# 17_RK3588_HDMI_eDP_Interface.net
KiCad netlist of a schematic drawn in Altium Designer
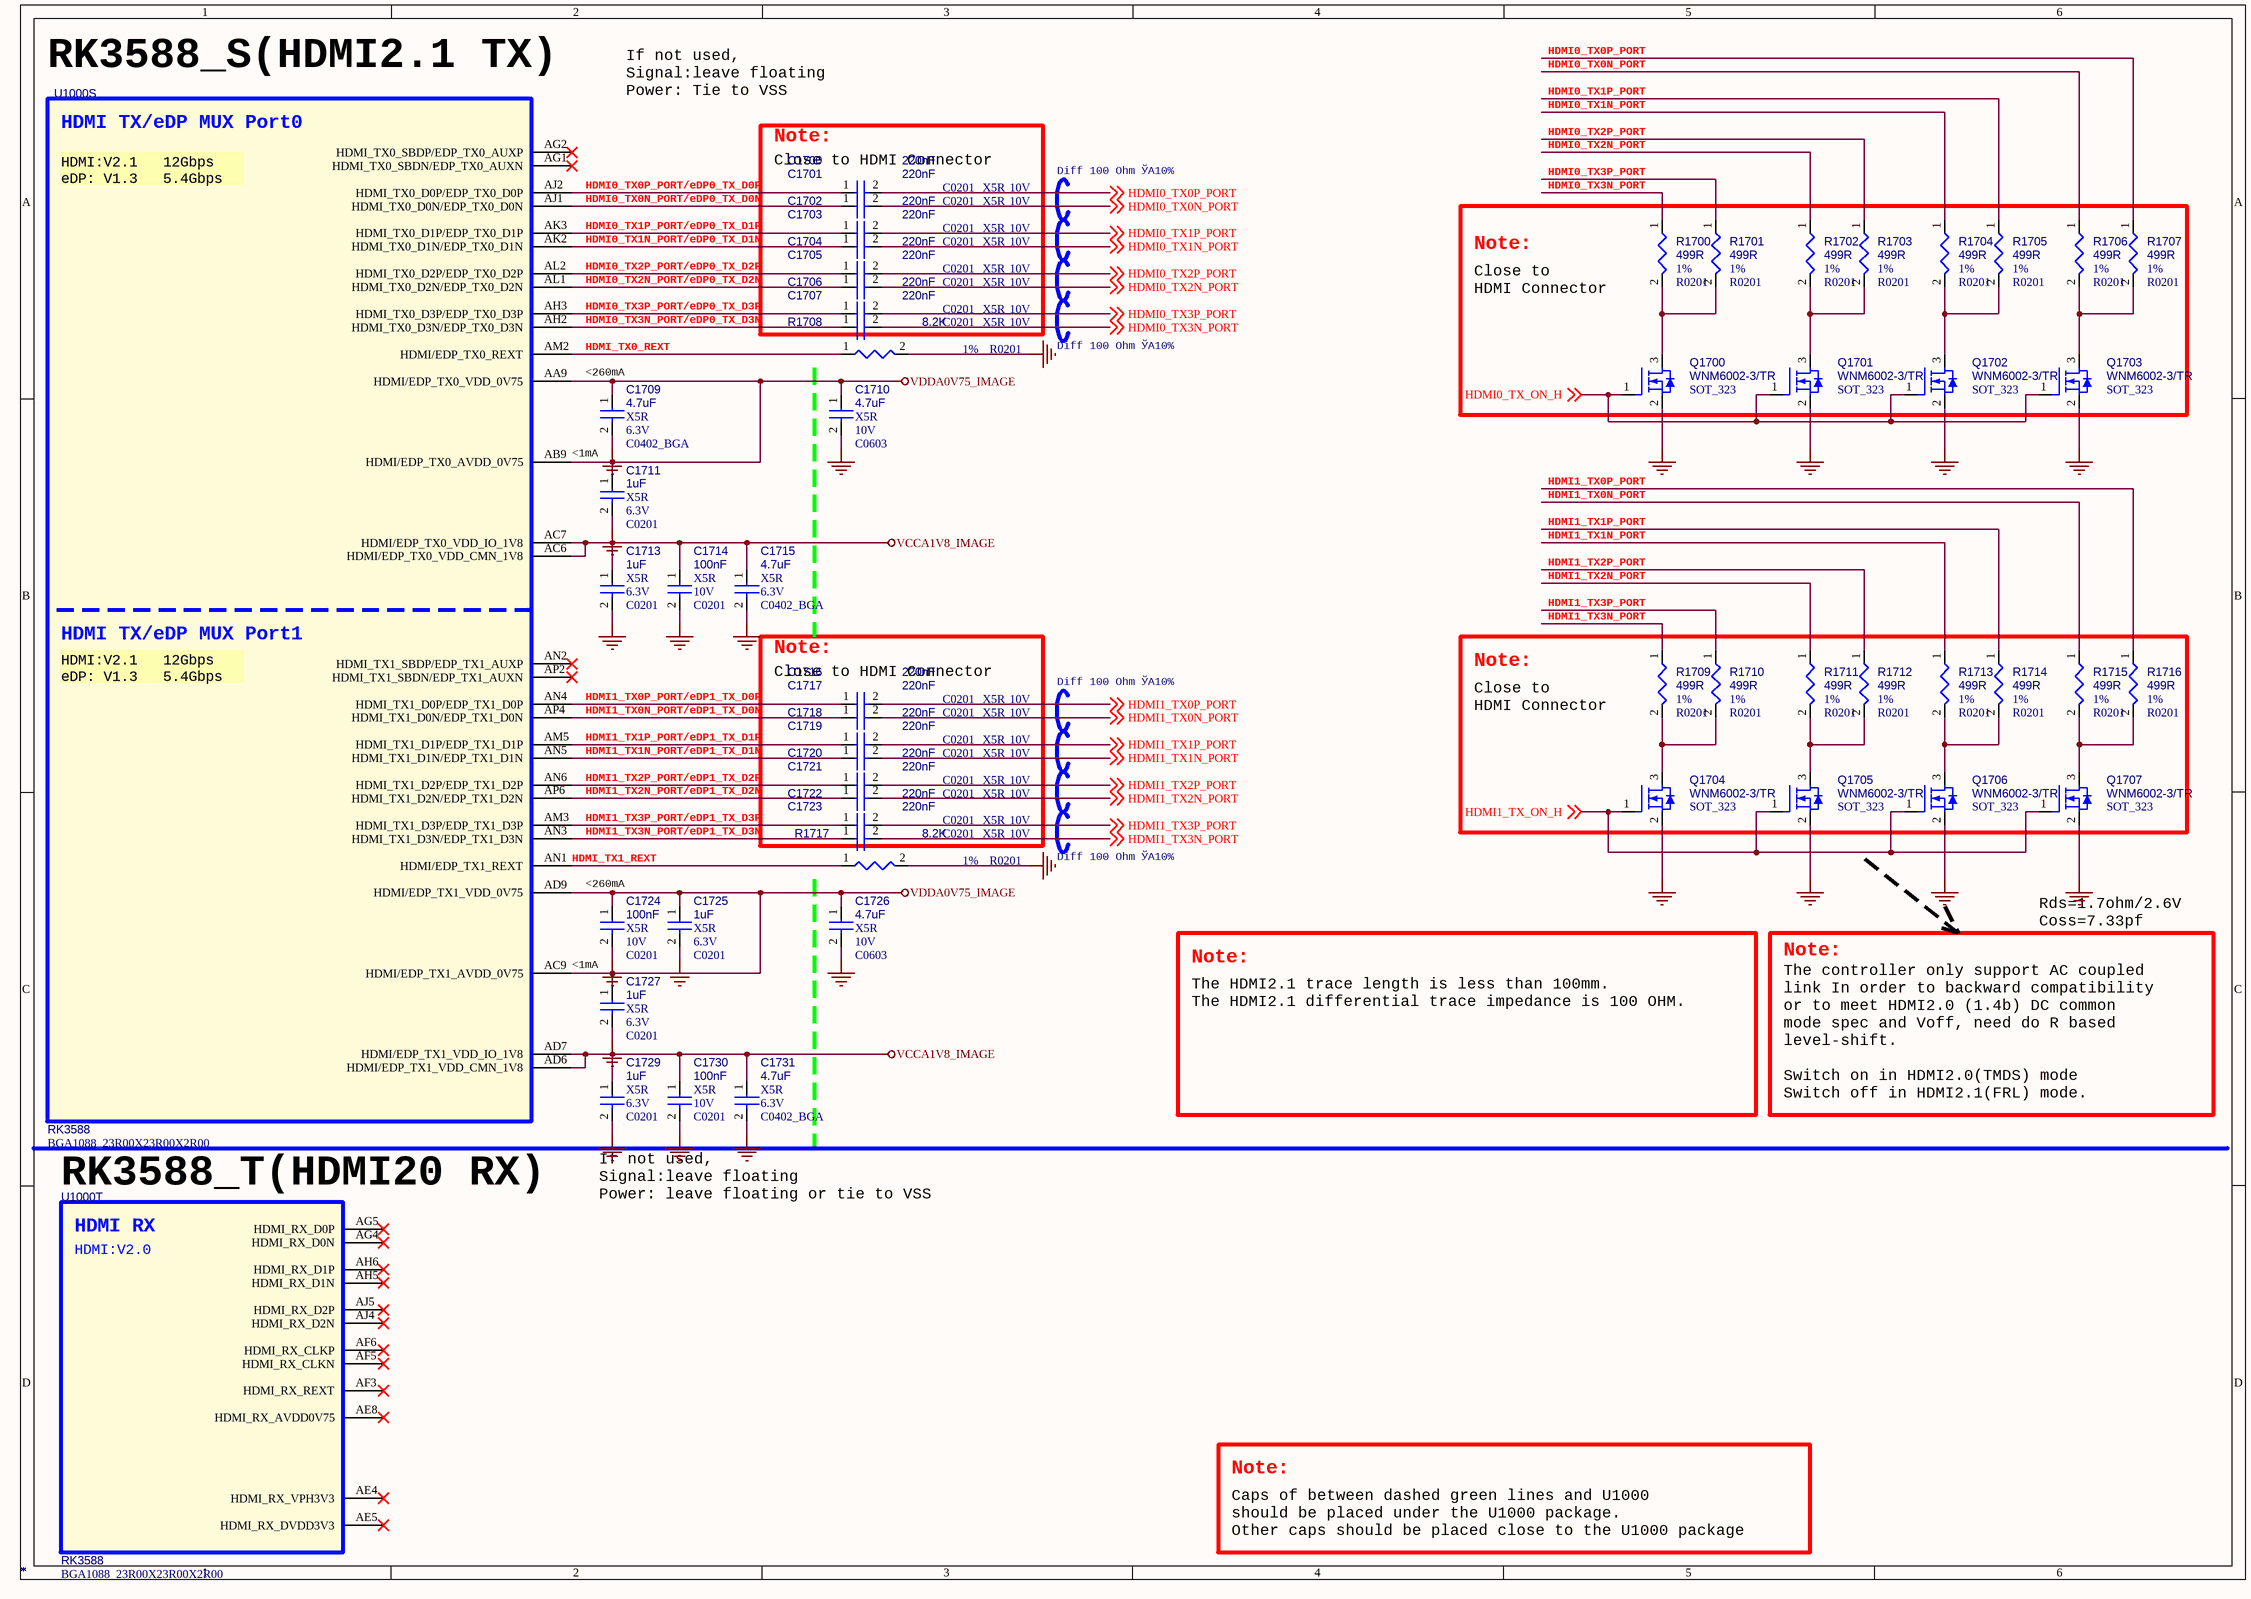
[diagram p0: 17.RK3588_HDMI_eDP Interface.SchDoc]

(export (version "E")
  (design (tool "Eeschema 10.0.6"))
  (components
    (comp (ref "C1700")
      (value "*")
      (footprint "C0201")
      (description "cap,220.00nF,+/-10%,10V,X5R,C0201")
      (fields
        (field (name "VOLTAGE") "10V")
        (field (name "PCB FOOTPRINT") "C0201")
        (field (name "DIELECTRIC") "X5R")
        (field (name "TOLERANCE") "10%")
        (field (name "MANUFACTURER") "TDK")
        (field (name "ALTIUM_UNNAMED_1") "220nF")
        (field (name "CREATED BY") "JJJ")
      )
      (libsource (lib "*") (part "CAP NP"))
    )
    (comp (ref "C1701")
      (value "*")
      (footprint "C0201")
      (description "cap,220.00nF,+/-10%,10V,X5R,C0201")
      (fields
        (field (name "VOLTAGE") "10V")
        (field (name "PCB FOOTPRINT") "C0201")
        (field (name "DIELECTRIC") "X5R")
        (field (name "MANUFACTURER") "TDK")
        (field (name "TOLERANCE") "10%")
        (field (name "ALTIUM_UNNAMED_1") "220nF")
        (field (name "CREATED BY") "JJJ")
      )
      (libsource (lib "*") (part "CAP NP"))
    )
    (comp (ref "C1702")
      (value "*")
      (footprint "C0201")
      (description "cap,220.00nF,+/-10%,10V,X5R,C0201")
      (fields
        (field (name "VOLTAGE") "10V")
        (field (name "PCB FOOTPRINT") "C0201")
        (field (name "DIELECTRIC") "X5R")
        (field (name "TOLERANCE") "10%")
        (field (name "MANUFACTURER") "TDK")
        (field (name "ALTIUM_UNNAMED_1") "220nF")
        (field (name "CREATED BY") "JJJ")
      )
      (libsource (lib "*") (part "CAP NP"))
    )
    (comp (ref "C1703")
      (value "*")
      (footprint "C0201")
      (description "cap,220.00nF,+/-10%,10V,X5R,C0201")
      (fields
        (field (name "VOLTAGE") "10V")
        (field (name "PCB FOOTPRINT") "C0201")
        (field (name "DIELECTRIC") "X5R")
        (field (name "MANUFACTURER") "TDK")
        (field (name "TOLERANCE") "10%")
        (field (name "ALTIUM_UNNAMED_1") "220nF")
        (field (name "CREATED BY") "JJJ")
      )
      (libsource (lib "*") (part "CAP NP"))
    )
    (comp (ref "C1704")
      (value "*")
      (footprint "C0201")
      (description "cap,220.00nF,+/-10%,10V,X5R,C0201")
      (fields
        (field (name "VOLTAGE") "10V")
        (field (name "PCB FOOTPRINT") "C0201")
        (field (name "DIELECTRIC") "X5R")
        (field (name "TOLERANCE") "10%")
        (field (name "MANUFACTURER") "TDK")
        (field (name "ALTIUM_UNNAMED_1") "220nF")
        (field (name "CREATED BY") "JJJ")
      )
      (libsource (lib "*") (part "CAP NP"))
    )
    (comp (ref "C1705")
      (value "*")
      (footprint "C0201")
      (description "cap,220.00nF,+/-10%,10V,X5R,C0201")
      (fields
        (field (name "VOLTAGE") "10V")
        (field (name "PCB FOOTPRINT") "C0201")
        (field (name "DIELECTRIC") "X5R")
        (field (name "MANUFACTURER") "TDK")
        (field (name "TOLERANCE") "10%")
        (field (name "ALTIUM_UNNAMED_1") "220nF")
        (field (name "CREATED BY") "JJJ")
      )
      (libsource (lib "*") (part "CAP NP"))
    )
    (comp (ref "C1706")
      (value "*")
      (footprint "C0201")
      (description "cap,220.00nF,+/-10%,10V,X5R,C0201")
      (fields
        (field (name "VOLTAGE") "10V")
        (field (name "PCB FOOTPRINT") "C0201")
        (field (name "DIELECTRIC") "X5R")
        (field (name "TOLERANCE") "10%")
        (field (name "MANUFACTURER") "TDK")
        (field (name "ALTIUM_UNNAMED_1") "220nF")
        (field (name "CREATED BY") "JJJ")
      )
      (libsource (lib "*") (part "CAP NP"))
    )
    (comp (ref "C1707")
      (value "*")
      (footprint "C0201")
      (description "cap,220.00nF,+/-10%,10V,X5R,C0201")
      (fields
        (field (name "VOLTAGE") "10V")
        (field (name "PCB FOOTPRINT") "C0201")
        (field (name "DIELECTRIC") "X5R")
        (field (name "TOLERANCE") "10%")
        (field (name "MANUFACTURER") "TDK")
        (field (name "ALTIUM_UNNAMED_1") "220nF")
        (field (name "CREATED BY") "JJJ")
      )
      (libsource (lib "*") (part "CAP NP"))
    )
    (comp (ref "C1709")
      (value "*")
      (footprint "C0402_BGA")
      (description "cap,4.70uF,+/-10%,6.3V,X5R,C0402")
      (fields
        (field (name "VOLTAGE") "6.3V")
        (field (name "PCB FOOTPRINT") "C0402_BGA")
        (field (name "DIELECTRIC") "X5R")
        (field (name "MANUFACTURER") "TDK")
        (field (name "TOLERANCE") "10%")
        (field (name "ALTIUM_UNNAMED_1") "4.7uF")
        (field (name "CREATED BY") "JJJ")
      )
      (libsource (lib "*") (part "CAP NP"))
    )
    (comp (ref "C1710")
      (value "*")
      (footprint "C0603")
      (description "cap,4.70uF,+/-10%,10V,X5R,C0603")
      (fields
        (field (name "VOLTAGE") "10V")
        (field (name "PCB FOOTPRINT") "C0603")
        (field (name "DIELECTRIC") "X5R")
        (field (name "MANUFACTURER") "TDK")
        (field (name "TOLERANCE") "10%")
        (field (name "ALTIUM_UNNAMED_1") "4.7uF")
        (field (name "CREATED BY") "JJJ")
      )
      (libsource (lib "*") (part "CAP NP"))
    )
    (comp (ref "C1711")
      (value "*")
      (footprint "C0201")
      (description "cap,1.00uF,+/-20%,6.3V,X5R,C0201")
      (fields
        (field (name "VOLTAGE") "6.3V")
        (field (name "PCB FOOTPRINT") "C0201")
        (field (name "DIELECTRIC") "X5R")
        (field (name "MANUFACTURER") "TDK")
        (field (name "TOLERANCE") "20%")
        (field (name "ALTIUM_UNNAMED_1") "1uF")
        (field (name "CREATED BY") "JJJ")
      )
      (libsource (lib "*") (part "CAP NP"))
    )
    (comp (ref "C1713")
      (value "*")
      (footprint "C0201")
      (description "cap,1.00uF,+/-20%,6.3V,X5R,C0201")
      (fields
        (field (name "VOLTAGE") "6.3V")
        (field (name "PCB FOOTPRINT") "C0201")
        (field (name "DIELECTRIC") "X5R")
        (field (name "TOLERANCE") "20%")
        (field (name "MANUFACTURER") "TDK")
        (field (name "ALTIUM_UNNAMED_1") "1uF")
        (field (name "CREATED BY") "JJJ")
      )
      (libsource (lib "*") (part "CAP NP"))
    )
    (comp (ref "C1714")
      (value "*")
      (footprint "C0201")
      (description "cap,100.00nF,+/-10%,10V,X5R,C0201")
      (fields
        (field (name "VOLTAGE") "10V")
        (field (name "PCB FOOTPRINT") "C0201")
        (field (name "DIELECTRIC") "X5R")
        (field (name "MANUFACTURER") "TDK")
        (field (name "TOLERANCE") "10%")
        (field (name "ALTIUM_UNNAMED_1") "100nF")
        (field (name "CREATED BY") "JJJ")
      )
      (libsource (lib "*") (part "CAP NP"))
    )
    (comp (ref "C1715")
      (value "*")
      (footprint "C0402_BGA")
      (description "cap,4.70uF,+/-10%,6.3V,X5R,C0402")
      (fields
        (field (name "VOLTAGE") "6.3V")
        (field (name "PCB FOOTPRINT") "C0402_BGA")
        (field (name "DIELECTRIC") "X5R")
        (field (name "TOLERANCE") "10%")
        (field (name "MANUFACTURER") "TDK")
        (field (name "ALTIUM_UNNAMED_1") "4.7uF")
        (field (name "CREATED BY") "JJJ")
      )
      (libsource (lib "*") (part "CAP NP"))
    )
    (comp (ref "C1716")
      (value "*")
      (footprint "C0201")
      (description "cap,220.00nF,+/-10%,10V,X5R,C0201")
      (fields
        (field (name "VOLTAGE") "10V")
        (field (name "PCB FOOTPRINT") "C0201")
        (field (name "DIELECTRIC") "X5R")
        (field (name "TOLERANCE") "10%")
        (field (name "MANUFACTURER") "TDK")
        (field (name "ALTIUM_UNNAMED_1") "220nF")
        (field (name "CREATED BY") "JJJ")
      )
      (libsource (lib "*") (part "CAP NP"))
    )
    (comp (ref "C1717")
      (value "*")
      (footprint "C0201")
      (description "cap,220.00nF,+/-10%,10V,X5R,C0201")
      (fields
        (field (name "VOLTAGE") "10V")
        (field (name "PCB FOOTPRINT") "C0201")
        (field (name "DIELECTRIC") "X5R")
        (field (name "MANUFACTURER") "TDK")
        (field (name "TOLERANCE") "10%")
        (field (name "ALTIUM_UNNAMED_1") "220nF")
        (field (name "CREATED BY") "JJJ")
      )
      (libsource (lib "*") (part "CAP NP"))
    )
    (comp (ref "C1718")
      (value "*")
      (footprint "C0201")
      (description "cap,220.00nF,+/-10%,10V,X5R,C0201")
      (fields
        (field (name "VOLTAGE") "10V")
        (field (name "PCB FOOTPRINT") "C0201")
        (field (name "DIELECTRIC") "X5R")
        (field (name "TOLERANCE") "10%")
        (field (name "MANUFACTURER") "TDK")
        (field (name "ALTIUM_UNNAMED_1") "220nF")
        (field (name "CREATED BY") "JJJ")
      )
      (libsource (lib "*") (part "CAP NP"))
    )
    (comp (ref "C1719")
      (value "*")
      (footprint "C0201")
      (description "cap,220.00nF,+/-10%,10V,X5R,C0201")
      (fields
        (field (name "VOLTAGE") "10V")
        (field (name "PCB FOOTPRINT") "C0201")
        (field (name "DIELECTRIC") "X5R")
        (field (name "MANUFACTURER") "TDK")
        (field (name "TOLERANCE") "10%")
        (field (name "ALTIUM_UNNAMED_1") "220nF")
        (field (name "CREATED BY") "JJJ")
      )
      (libsource (lib "*") (part "CAP NP"))
    )
    (comp (ref "C1720")
      (value "*")
      (footprint "C0201")
      (description "cap,220.00nF,+/-10%,10V,X5R,C0201")
      (fields
        (field (name "VOLTAGE") "10V")
        (field (name "PCB FOOTPRINT") "C0201")
        (field (name "DIELECTRIC") "X5R")
        (field (name "TOLERANCE") "10%")
        (field (name "MANUFACTURER") "TDK")
        (field (name "ALTIUM_UNNAMED_1") "220nF")
        (field (name "CREATED BY") "JJJ")
      )
      (libsource (lib "*") (part "CAP NP"))
    )
    (comp (ref "C1721")
      (value "*")
      (footprint "C0201")
      (description "cap,220.00nF,+/-10%,10V,X5R,C0201")
      (fields
        (field (name "VOLTAGE") "10V")
        (field (name "PCB FOOTPRINT") "C0201")
        (field (name "DIELECTRIC") "X5R")
        (field (name "MANUFACTURER") "TDK")
        (field (name "TOLERANCE") "10%")
        (field (name "ALTIUM_UNNAMED_1") "220nF")
        (field (name "CREATED BY") "JJJ")
      )
      (libsource (lib "*") (part "CAP NP"))
    )
    (comp (ref "C1722")
      (value "*")
      (footprint "C0201")
      (description "cap,220.00nF,+/-10%,10V,X5R,C0201")
      (fields
        (field (name "VOLTAGE") "10V")
        (field (name "PCB FOOTPRINT") "C0201")
        (field (name "DIELECTRIC") "X5R")
        (field (name "TOLERANCE") "10%")
        (field (name "MANUFACTURER") "TDK")
        (field (name "ALTIUM_UNNAMED_1") "220nF")
        (field (name "CREATED BY") "JJJ")
      )
      (libsource (lib "*") (part "CAP NP"))
    )
    (comp (ref "C1723")
      (value "*")
      (footprint "C0201")
      (description "cap,220.00nF,+/-10%,10V,X5R,C0201")
      (fields
        (field (name "VOLTAGE") "10V")
        (field (name "PCB FOOTPRINT") "C0201")
        (field (name "DIELECTRIC") "X5R")
        (field (name "TOLERANCE") "10%")
        (field (name "MANUFACTURER") "TDK")
        (field (name "ALTIUM_UNNAMED_1") "220nF")
        (field (name "CREATED BY") "JJJ")
      )
      (libsource (lib "*") (part "CAP NP"))
    )
    (comp (ref "C1724")
      (value "*")
      (footprint "C0201")
      (description "cap,100.00nF,+/-10%,10V,X5R,C0201")
      (fields
        (field (name "VOLTAGE") "10V")
        (field (name "PCB FOOTPRINT") "C0201")
        (field (name "DIELECTRIC") "X5R")
        (field (name "MANUFACTURER") "TDK")
        (field (name "TOLERANCE") "10%")
        (field (name "ALTIUM_UNNAMED_1") "100nF")
        (field (name "CREATED BY") "JJJ")
      )
      (libsource (lib "*") (part "CAP NP"))
    )
    (comp (ref "C1725")
      (value "*")
      (footprint "C0201")
      (description "cap,1.00uF,+/-20%,6.3V,X5R,C0201")
      (fields
        (field (name "VOLTAGE") "6.3V")
        (field (name "PCB FOOTPRINT") "C0201")
        (field (name "DIELECTRIC") "X5R")
        (field (name "TOLERANCE") "20%")
        (field (name "MANUFACTURER") "TDK")
        (field (name "ALTIUM_UNNAMED_1") "1uF")
        (field (name "CREATED BY") "JJJ")
      )
      (libsource (lib "*") (part "CAP NP"))
    )
    (comp (ref "C1726")
      (value "*")
      (footprint "C0603")
      (description "cap,4.70uF,+/-10%,10V,X5R,C0603")
      (fields
        (field (name "VOLTAGE") "10V")
        (field (name "PCB FOOTPRINT") "C0603")
        (field (name "DIELECTRIC") "X5R")
        (field (name "TOLERANCE") "10%")
        (field (name "MANUFACTURER") "TDK")
        (field (name "ALTIUM_UNNAMED_1") "4.7uF")
        (field (name "CREATED BY") "JJJ")
      )
      (libsource (lib "*") (part "CAP NP"))
    )
    (comp (ref "C1727")
      (value "*")
      (footprint "C0201")
      (description "cap,1.00uF,+/-20%,6.3V,X5R,C0201")
      (fields
        (field (name "VOLTAGE") "6.3V")
        (field (name "PCB FOOTPRINT") "C0201")
        (field (name "DIELECTRIC") "X5R")
        (field (name "MANUFACTURER") "TDK")
        (field (name "TOLERANCE") "20%")
        (field (name "ALTIUM_UNNAMED_1") "1uF")
        (field (name "CREATED BY") "JJJ")
      )
      (libsource (lib "*") (part "CAP NP"))
    )
    (comp (ref "C1729")
      (value "*")
      (footprint "C0201")
      (description "cap,1.00uF,+/-20%,6.3V,X5R,C0201")
      (fields
        (field (name "VOLTAGE") "6.3V")
        (field (name "PCB FOOTPRINT") "C0201")
        (field (name "DIELECTRIC") "X5R")
        (field (name "TOLERANCE") "20%")
        (field (name "MANUFACTURER") "TDK")
        (field (name "ALTIUM_UNNAMED_1") "1uF")
        (field (name "CREATED BY") "JJJ")
      )
      (libsource (lib "*") (part "CAP NP"))
    )
    (comp (ref "C1730")
      (value "*")
      (footprint "C0201")
      (description "cap,100.00nF,+/-10%,10V,X5R,C0201")
      (fields
        (field (name "VOLTAGE") "10V")
        (field (name "PCB FOOTPRINT") "C0201")
        (field (name "DIELECTRIC") "X5R")
        (field (name "MANUFACTURER") "TDK")
        (field (name "TOLERANCE") "10%")
        (field (name "ALTIUM_UNNAMED_1") "100nF")
        (field (name "CREATED BY") "JJJ")
      )
      (libsource (lib "*") (part "CAP NP"))
    )
    (comp (ref "C1731")
      (value "*")
      (footprint "C0402_BGA")
      (description "cap,4.70uF,+/-10%,6.3V,X5R,C0402")
      (fields
        (field (name "VOLTAGE") "6.3V")
        (field (name "PCB FOOTPRINT") "C0402_BGA")
        (field (name "DIELECTRIC") "X5R")
        (field (name "TOLERANCE") "10%")
        (field (name "MANUFACTURER") "TDK")
        (field (name "ALTIUM_UNNAMED_1") "4.7uF")
        (field (name "CREATED BY") "JJJ")
      )
      (libsource (lib "*") (part "CAP NP"))
    )
    (comp (ref "Q1700")
      (value "*")
      (footprint "SOT23")
      (description "NMOS,WNM6002-3/TR,SOT_323,Id=0.3A,Vds=60V")
      (fields
        (field (name "PCB FOOTPRINT") "SOT_323")
        (field (name "MANUFACTURER") "WillSemi(О¤¶ы°лµјМе)")
        (field (name "ALTIUM_UNNAMED_1") "WNM6002-3/TR")
        (field (name "CREATED BY") "JJJ")
      )
      (libsource (lib "*") (part "MOSFET N"))
    )
    (comp (ref "Q1701")
      (value "*")
      (footprint "SOT23")
      (description "NMOS,WNM6002-3/TR,SOT_323,Id=0.3A,Vds=60V")
      (fields
        (field (name "PCB FOOTPRINT") "SOT_323")
        (field (name "MANUFACTURER") "WillSemi(О¤¶ы°лµјМе)")
        (field (name "ALTIUM_UNNAMED_1") "WNM6002-3/TR")
        (field (name "CREATED BY") "JJJ")
      )
      (libsource (lib "*") (part "MOSFET N"))
    )
    (comp (ref "Q1702")
      (value "*")
      (footprint "SOT23")
      (description "NMOS,WNM6002-3/TR,SOT_323,Id=0.3A,Vds=60V")
      (fields
        (field (name "PCB FOOTPRINT") "SOT_323")
        (field (name "MANUFACTURER") "WillSemi(О¤¶ы°лµјМе)")
        (field (name "ALTIUM_UNNAMED_1") "WNM6002-3/TR")
        (field (name "CREATED BY") "JJJ")
      )
      (libsource (lib "*") (part "MOSFET N"))
    )
    (comp (ref "Q1703")
      (value "*")
      (footprint "SOT23")
      (description "NMOS,WNM6002-3/TR,SOT_323,Id=0.3A,Vds=60V")
      (fields
        (field (name "PCB FOOTPRINT") "SOT_323")
        (field (name "MANUFACTURER") "WillSemi(О¤¶ы°лµјМе)")
        (field (name "ALTIUM_UNNAMED_1") "WNM6002-3/TR")
        (field (name "CREATED BY") "JJJ")
      )
      (libsource (lib "*") (part "MOSFET N"))
    )
    (comp (ref "Q1704")
      (value "*")
      (footprint "SOT23")
      (description "NMOS,WNM6002-3/TR,SOT_323,Id=0.3A,Vds=60V")
      (fields
        (field (name "PCB FOOTPRINT") "SOT_323")
        (field (name "MANUFACTURER") "WillSemi(О¤¶ы°лµјМе)")
        (field (name "ALTIUM_UNNAMED_1") "WNM6002-3/TR")
        (field (name "CREATED BY") "JJJ")
      )
      (libsource (lib "*") (part "MOSFET N"))
    )
    (comp (ref "Q1705")
      (value "*")
      (footprint "SOT23")
      (description "NMOS,WNM6002-3/TR,SOT_323,Id=0.3A,Vds=60V")
      (fields
        (field (name "PCB FOOTPRINT") "SOT_323")
        (field (name "MANUFACTURER") "WillSemi(О¤¶ы°лµјМе)")
        (field (name "ALTIUM_UNNAMED_1") "WNM6002-3/TR")
        (field (name "CREATED BY") "JJJ")
      )
      (libsource (lib "*") (part "MOSFET N"))
    )
    (comp (ref "Q1706")
      (value "*")
      (footprint "SOT23")
      (description "NMOS,WNM6002-3/TR,SOT_323,Id=0.3A,Vds=60V")
      (fields
        (field (name "PCB FOOTPRINT") "SOT_323")
        (field (name "MANUFACTURER") "WillSemi(О¤¶ы°лµјМе)")
        (field (name "ALTIUM_UNNAMED_1") "WNM6002-3/TR")
        (field (name "CREATED BY") "JJJ")
      )
      (libsource (lib "*") (part "MOSFET N"))
    )
    (comp (ref "Q1707")
      (value "*")
      (footprint "SOT23")
      (description "NMOS,WNM6002-3/TR,SOT_323,Id=0.3A,Vds=60V")
      (fields
        (field (name "PCB FOOTPRINT") "SOT_323")
        (field (name "MANUFACTURER") "WillSemi(О¤¶ы°лµјМе)")
        (field (name "ALTIUM_UNNAMED_1") "WNM6002-3/TR")
        (field (name "CREATED BY") "JJJ")
      )
      (libsource (lib "*") (part "MOSFET N"))
    )
    (comp (ref "R1700")
      (value "*")
      (footprint "R0402")
      (description "НЁУГєсД¤µзЧи,499R,+/-1%,R0201,1/20W.")
      (fields
        (field (name "PCB FOOTPRINT") "R0201")
        (field (name "TOLERANCE") "1%")
        (field (name "MANUFACTURER") "YAGEO")
        (field (name "ALTIUM_UNNAMED_1") "499R")
        (field (name "CREATED BY") "YTL")
      )
      (libsource (lib "*") (part "RESISTOR_Dup1"))
    )
    (comp (ref "R1701")
      (value "*")
      (footprint "R0402")
      (description "НЁУГєсД¤µзЧи,499R,+/-1%,R0201,1/20W.")
      (fields
        (field (name "PCB FOOTPRINT") "R0201")
        (field (name "TOLERANCE") "1%")
        (field (name "MANUFACTURER") "YAGEO")
        (field (name "ALTIUM_UNNAMED_1") "499R")
        (field (name "CREATED BY") "YTL")
      )
      (libsource (lib "*") (part "RESISTOR_Dup1"))
    )
    (comp (ref "R1702")
      (value "*")
      (footprint "R0402")
      (description "НЁУГєсД¤µзЧи,499R,+/-1%,R0201,1/20W.")
      (fields
        (field (name "PCB FOOTPRINT") "R0201")
        (field (name "TOLERANCE") "1%")
        (field (name "MANUFACTURER") "YAGEO")
        (field (name "ALTIUM_UNNAMED_1") "499R")
        (field (name "CREATED BY") "YTL")
      )
      (libsource (lib "*") (part "RESISTOR_Dup1"))
    )
    (comp (ref "R1703")
      (value "*")
      (footprint "R0402")
      (description "НЁУГєсД¤µзЧи,499R,+/-1%,R0201,1/20W.")
      (fields
        (field (name "PCB FOOTPRINT") "R0201")
        (field (name "TOLERANCE") "1%")
        (field (name "MANUFACTURER") "YAGEO")
        (field (name "ALTIUM_UNNAMED_1") "499R")
        (field (name "CREATED BY") "YTL")
      )
      (libsource (lib "*") (part "RESISTOR_Dup1"))
    )
    (comp (ref "R1704")
      (value "*")
      (footprint "R0402")
      (description "НЁУГєсД¤µзЧи,499R,+/-1%,R0201,1/20W.")
      (fields
        (field (name "PCB FOOTPRINT") "R0201")
        (field (name "TOLERANCE") "1%")
        (field (name "MANUFACTURER") "YAGEO")
        (field (name "ALTIUM_UNNAMED_1") "499R")
        (field (name "CREATED BY") "YTL")
      )
      (libsource (lib "*") (part "RESISTOR_Dup1"))
    )
    (comp (ref "R1705")
      (value "*")
      (footprint "R0402")
      (description "НЁУГєсД¤µзЧи,499R,+/-1%,R0201,1/20W.")
      (fields
        (field (name "PCB FOOTPRINT") "R0201")
        (field (name "TOLERANCE") "1%")
        (field (name "MANUFACTURER") "YAGEO")
        (field (name "ALTIUM_UNNAMED_1") "499R")
        (field (name "CREATED BY") "YTL")
      )
      (libsource (lib "*") (part "RESISTOR_Dup1"))
    )
    (comp (ref "R1706")
      (value "*")
      (footprint "R0402")
      (description "НЁУГєсД¤µзЧи,499R,+/-1%,R0201,1/20W.")
      (fields
        (field (name "PCB FOOTPRINT") "R0201")
        (field (name "TOLERANCE") "1%")
        (field (name "MANUFACTURER") "YAGEO")
        (field (name "ALTIUM_UNNAMED_1") "499R")
        (field (name "CREATED BY") "YTL")
      )
      (libsource (lib "*") (part "RESISTOR_Dup1"))
    )
    (comp (ref "R1707")
      (value "*")
      (footprint "R0402")
      (description "НЁУГєсД¤µзЧи,499R,+/-1%,R0201,1/20W.")
      (fields
        (field (name "PCB FOOTPRINT") "R0201")
        (field (name "TOLERANCE") "1%")
        (field (name "MANUFACTURER") "YAGEO")
        (field (name "ALTIUM_UNNAMED_1") "499R")
        (field (name "CREATED BY") "YTL")
      )
      (libsource (lib "*") (part "RESISTOR_Dup1"))
    )
    (comp (ref "R1708")
      (value "*")
      (footprint "R0402")
      (description "НЁУГєсД¤µзЧи,8K2,+/-1%,R0201,1/20W.")
      (fields
        (field (name "PCB FOOTPRINT") "R0201")
        (field (name "TOLERANCE") "1%")
        (field (name "MANUFACTURER") "YAGEO")
        (field (name "ALTIUM_UNNAMED_1") "8.2K")
        (field (name "CREATED BY") "YTL")
      )
      (libsource (lib "*") (part "RESISTOR_Dup1"))
    )
    (comp (ref "R1709")
      (value "*")
      (footprint "R0402")
      (description "НЁУГєсД¤µзЧи,499R,+/-1%,R0201,1/20W.")
      (fields
        (field (name "PCB FOOTPRINT") "R0201")
        (field (name "TOLERANCE") "1%")
        (field (name "MANUFACTURER") "YAGEO")
        (field (name "ALTIUM_UNNAMED_1") "499R")
        (field (name "CREATED BY") "YTL")
      )
      (libsource (lib "*") (part "RESISTOR_Dup1"))
    )
    (comp (ref "R1710")
      (value "*")
      (footprint "R0402")
      (description "НЁУГєсД¤µзЧи,499R,+/-1%,R0201,1/20W.")
      (fields
        (field (name "PCB FOOTPRINT") "R0201")
        (field (name "TOLERANCE") "1%")
        (field (name "MANUFACTURER") "YAGEO")
        (field (name "ALTIUM_UNNAMED_1") "499R")
        (field (name "CREATED BY") "YTL")
      )
      (libsource (lib "*") (part "RESISTOR_Dup1"))
    )
    (comp (ref "R1711")
      (value "*")
      (footprint "R0402")
      (description "НЁУГєсД¤µзЧи,499R,+/-1%,R0201,1/20W.")
      (fields
        (field (name "PCB FOOTPRINT") "R0201")
        (field (name "TOLERANCE") "1%")
        (field (name "MANUFACTURER") "YAGEO")
        (field (name "ALTIUM_UNNAMED_1") "499R")
        (field (name "CREATED BY") "YTL")
      )
      (libsource (lib "*") (part "RESISTOR_Dup1"))
    )
    (comp (ref "R1712")
      (value "*")
      (footprint "R0402")
      (description "НЁУГєсД¤µзЧи,499R,+/-1%,R0201,1/20W.")
      (fields
        (field (name "PCB FOOTPRINT") "R0201")
        (field (name "TOLERANCE") "1%")
        (field (name "MANUFACTURER") "YAGEO")
        (field (name "ALTIUM_UNNAMED_1") "499R")
        (field (name "CREATED BY") "YTL")
      )
      (libsource (lib "*") (part "RESISTOR_Dup1"))
    )
    (comp (ref "R1713")
      (value "*")
      (footprint "R0402")
      (description "НЁУГєсД¤µзЧи,499R,+/-1%,R0201,1/20W.")
      (fields
        (field (name "PCB FOOTPRINT") "R0201")
        (field (name "TOLERANCE") "1%")
        (field (name "MANUFACTURER") "YAGEO")
        (field (name "ALTIUM_UNNAMED_1") "499R")
        (field (name "CREATED BY") "YTL")
      )
      (libsource (lib "*") (part "RESISTOR_Dup1"))
    )
    (comp (ref "R1714")
      (value "*")
      (footprint "R0402")
      (description "НЁУГєсД¤µзЧи,499R,+/-1%,R0201,1/20W.")
      (fields
        (field (name "PCB FOOTPRINT") "R0201")
        (field (name "TOLERANCE") "1%")
        (field (name "MANUFACTURER") "YAGEO")
        (field (name "ALTIUM_UNNAMED_1") "499R")
        (field (name "CREATED BY") "YTL")
      )
      (libsource (lib "*") (part "RESISTOR_Dup1"))
    )
    (comp (ref "R1715")
      (value "*")
      (footprint "R0402")
      (description "НЁУГєсД¤µзЧи,499R,+/-1%,R0201,1/20W.")
      (fields
        (field (name "PCB FOOTPRINT") "R0201")
        (field (name "TOLERANCE") "1%")
        (field (name "MANUFACTURER") "YAGEO")
        (field (name "ALTIUM_UNNAMED_1") "499R")
        (field (name "CREATED BY") "YTL")
      )
      (libsource (lib "*") (part "RESISTOR_Dup1"))
    )
    (comp (ref "R1716")
      (value "*")
      (footprint "R0402")
      (description "НЁУГєсД¤µзЧи,499R,+/-1%,R0201,1/20W.")
      (fields
        (field (name "PCB FOOTPRINT") "R0201")
        (field (name "TOLERANCE") "1%")
        (field (name "MANUFACTURER") "YAGEO")
        (field (name "ALTIUM_UNNAMED_1") "499R")
        (field (name "CREATED BY") "YTL")
      )
      (libsource (lib "*") (part "RESISTOR_Dup1"))
    )
    (comp (ref "R1717")
      (value "*")
      (footprint "R0402")
      (description "НЁУГєсД¤µзЧи,8K2,+/-1%,R0201,1/20W.")
      (fields
        (field (name "PCB FOOTPRINT") "R0201")
        (field (name "TOLERANCE") "1%")
        (field (name "MANUFACTURER") "YAGEO")
        (field (name "ALTIUM_UNNAMED_1") "8.2K")
        (field (name "CREATED BY") "YTL")
      )
      (libsource (lib "*") (part "RESISTOR_Dup1"))
    )
    (comp (ref "U1000")
      (value "*")
      (footprint "BGA1088_23R00X23R00X2R00")
      (description "ROCKCHIP SOC")
      (fields
        (field (name "MANUFACTURER") "Rockchip (ИрРѕОў)")
        (field (name "PCB FOOTPRINT") "BGA1088_23R00X23R00X2R00")
        (field (name "ALTIUM_UNNAMED_1") "RK3588")
        (field (name "CREATED BY") "YWQ")
      )
      (libsource (lib "*") (part "SOC_RK3588"))
    )
  )
  (nets
    (net (code "1") (name "/HDMI0_TX0N_PORT{slash}eDP0_TX_D0N") (class "Default")
      (node (ref "C1701") (pin "1") (pinfunction "1_1") (pintype "passive"))
      (node (ref "U1000") (pin "AJ1") (pinfunction "HDMI_TX0_D0N/EDP_TX0_D0N_AJ1") (pintype "passive"))
    )
    (net (code "2") (name "/HDMI0_TX0P_PORT{slash}eDP0_TX_D0P") (class "Default")
      (node (ref "C1700") (pin "1") (pinfunction "1_1") (pintype "passive"))
      (node (ref "U1000") (pin "AJ2") (pinfunction "HDMI_TX0_D0P/EDP_TX0_D0P_AJ2") (pintype "passive"))
    )
    (net (code "3") (name "/HDMI0_TX1N_PORT{slash}eDP0_TX_D1N") (class "Default")
      (node (ref "C1703") (pin "1") (pinfunction "1_1") (pintype "passive"))
      (node (ref "U1000") (pin "AK2") (pinfunction "HDMI_TX0_D1N/EDP_TX0_D1N_AK2") (pintype "passive"))
    )
    (net (code "4") (name "/HDMI0_TX1P_PORT{slash}eDP0_TX_D1P") (class "Default")
      (node (ref "C1702") (pin "1") (pinfunction "1_1") (pintype "passive"))
      (node (ref "U1000") (pin "AK3") (pinfunction "HDMI_TX0_D1P/EDP_TX0_D1P_AK3") (pintype "passive"))
    )
    (net (code "5") (name "/HDMI0_TX2N_PORT{slash}eDP0_TX_D2N") (class "Default")
      (node (ref "C1705") (pin "1") (pinfunction "1_1") (pintype "passive"))
      (node (ref "U1000") (pin "AL1") (pinfunction "HDMI_TX0_D2N/EDP_TX0_D2N_AL1") (pintype "passive"))
    )
    (net (code "6") (name "/HDMI0_TX2P_PORT{slash}eDP0_TX_D2P") (class "Default")
      (node (ref "C1704") (pin "1") (pinfunction "1_1") (pintype "passive"))
      (node (ref "U1000") (pin "AL2") (pinfunction "HDMI_TX0_D2P/EDP_TX0_D2P_AL2") (pintype "passive"))
    )
    (net (code "7") (name "/HDMI0_TX3N_PORT{slash}eDP0_TX_D3N") (class "Default")
      (node (ref "C1707") (pin "1") (pinfunction "1_1") (pintype "passive"))
      (node (ref "U1000") (pin "AH2") (pinfunction "HDMI_TX0_D3N/EDP_TX0_D3N_AH2") (pintype "passive"))
    )
    (net (code "8") (name "/HDMI0_TX3P_PORT{slash}eDP0_TX_D3P") (class "Default")
      (node (ref "C1706") (pin "1") (pinfunction "1_1") (pintype "passive"))
      (node (ref "U1000") (pin "AH3") (pinfunction "HDMI_TX0_D3P/EDP_TX0_D3P_AH3") (pintype "passive"))
    )
    (net (code "9") (name "/HDMI1_TX0N_PORT{slash}eDP1_TX_D0N") (class "Default")
      (node (ref "C1717") (pin "1") (pinfunction "1_1") (pintype "passive"))
      (node (ref "U1000") (pin "AP4") (pinfunction "HDMI_TX1_D0N/EDP_TX1_D0N_AP4") (pintype "passive"))
    )
    (net (code "10") (name "/HDMI1_TX0P_PORT{slash}eDP1_TX_D0P") (class "Default")
      (node (ref "C1716") (pin "1") (pinfunction "1_1") (pintype "passive"))
      (node (ref "U1000") (pin "AN4") (pinfunction "HDMI_TX1_D0P/EDP_TX1_D0P_AN4") (pintype "passive"))
    )
    (net (code "11") (name "/HDMI1_TX1N_PORT{slash}eDP1_TX_D1N") (class "Default")
      (node (ref "C1719") (pin "1") (pinfunction "1_1") (pintype "passive"))
      (node (ref "U1000") (pin "AN5") (pinfunction "HDMI_TX1_D1N/EDP_TX1_D1N_AN5") (pintype "passive"))
    )
    (net (code "12") (name "/HDMI1_TX1P_PORT{slash}eDP1_TX_D1P") (class "Default")
      (node (ref "C1718") (pin "1") (pinfunction "1_1") (pintype "passive"))
      (node (ref "U1000") (pin "AM5") (pinfunction "HDMI_TX1_D1P/EDP_TX1_D1P_AM5") (pintype "passive"))
    )
    (net (code "13") (name "/HDMI1_TX2N_PORT{slash}eDP1_TX_D2N") (class "Default")
      (node (ref "C1721") (pin "1") (pinfunction "1_1") (pintype "passive"))
      (node (ref "U1000") (pin "AP6") (pinfunction "HDMI_TX1_D2N/EDP_TX1_D2N_AP6") (pintype "passive"))
    )
    (net (code "14") (name "/HDMI1_TX2P_PORT{slash}eDP1_TX_D2P") (class "Default")
      (node (ref "C1720") (pin "1") (pinfunction "1_1") (pintype "passive"))
      (node (ref "U1000") (pin "AN6") (pinfunction "HDMI_TX1_D2P/EDP_TX1_D2P_AN6") (pintype "passive"))
    )
    (net (code "15") (name "/HDMI1_TX3N_PORT{slash}eDP1_TX_D3N") (class "Default")
      (node (ref "C1723") (pin "1") (pinfunction "1_1") (pintype "passive"))
      (node (ref "U1000") (pin "AN3") (pinfunction "HDMI_TX1_D3N/EDP_TX1_D3N_AN3") (pintype "passive"))
    )
    (net (code "16") (name "/HDMI1_TX3P_PORT{slash}eDP1_TX_D3P") (class "Default")
      (node (ref "C1722") (pin "1") (pinfunction "1_1") (pintype "passive"))
      (node (ref "U1000") (pin "AM3") (pinfunction "HDMI_TX1_D3P/EDP_TX1_D3P_AM3") (pintype "passive"))
    )
    (net (code "17") (name "/HDMI_TX0_REXT") (class "Default")
      (node (ref "R1708") (pin "1") (pinfunction "1_1") (pintype "passive"))
      (node (ref "U1000") (pin "AM2") (pinfunction "HDMI/EDP_TX0_REXT_AM2") (pintype "passive"))
    )
    (net (code "18") (name "/HDMI_TX1_REXT") (class "Default")
      (node (ref "R1717") (pin "1") (pinfunction "1_1") (pintype "passive"))
      (node (ref "U1000") (pin "AN1") (pinfunction "HDMI/EDP_TX1_REXT_AN1") (pintype "passive"))
    )
    (net (code "19") (name "GND") (class "Default")
      (node (ref "C1709") (pin "2") (pinfunction "2_2") (pintype "passive"))
      (node (ref "C1710") (pin "2") (pinfunction "2_2") (pintype "passive"))
      (node (ref "C1711") (pin "2") (pinfunction "2_2") (pintype "passive"))
      (node (ref "C1713") (pin "2") (pinfunction "2_2") (pintype "passive"))
      (node (ref "C1714") (pin "2") (pinfunction "2_2") (pintype "passive"))
      (node (ref "C1715") (pin "2") (pinfunction "2_2") (pintype "passive"))
      (node (ref "C1724") (pin "2") (pinfunction "2_2") (pintype "passive"))
      (node (ref "C1725") (pin "2") (pinfunction "2_2") (pintype "passive"))
      (node (ref "C1726") (pin "2") (pinfunction "2_2") (pintype "passive"))
      (node (ref "C1727") (pin "2") (pinfunction "2_2") (pintype "passive"))
      (node (ref "C1729") (pin "2") (pinfunction "2_2") (pintype "passive"))
      (node (ref "C1730") (pin "2") (pinfunction "2_2") (pintype "passive"))
      (node (ref "C1731") (pin "2") (pinfunction "2_2") (pintype "passive"))
      (node (ref "Q1700") (pin "2") (pinfunction "SOURCE_2") (pintype "passive"))
      (node (ref "Q1701") (pin "2") (pinfunction "SOURCE_2") (pintype "passive"))
      (node (ref "Q1702") (pin "2") (pinfunction "SOURCE_2") (pintype "passive"))
      (node (ref "Q1703") (pin "2") (pinfunction "SOURCE_2") (pintype "passive"))
      (node (ref "Q1704") (pin "2") (pinfunction "SOURCE_2") (pintype "passive"))
      (node (ref "Q1705") (pin "2") (pinfunction "SOURCE_2") (pintype "passive"))
      (node (ref "Q1706") (pin "2") (pinfunction "SOURCE_2") (pintype "passive"))
      (node (ref "Q1707") (pin "2") (pinfunction "SOURCE_2") (pintype "passive"))
      (node (ref "R1708") (pin "2") (pinfunction "2_2") (pintype "passive"))
      (node (ref "R1717") (pin "2") (pinfunction "2_2") (pintype "passive"))
    )
    (net (code "20") (name "HDMI0_TX0N_PORT") (class "Default")
      (node (ref "C1701") (pin "2") (pinfunction "2_2") (pintype "passive"))
      (node (ref "R1706") (pin "1") (pinfunction "1_1") (pintype "passive"))
    )
    (net (code "21") (name "HDMI0_TX0P_PORT") (class "Default")
      (node (ref "C1700") (pin "2") (pinfunction "2_2") (pintype "passive"))
      (node (ref "R1707") (pin "1") (pinfunction "1_1") (pintype "passive"))
    )
    (net (code "22") (name "HDMI0_TX1N_PORT") (class "Default")
      (node (ref "C1703") (pin "2") (pinfunction "2_2") (pintype "passive"))
      (node (ref "R1704") (pin "1") (pinfunction "1_1") (pintype "passive"))
    )
    (net (code "23") (name "HDMI0_TX1P_PORT") (class "Default")
      (node (ref "C1702") (pin "2") (pinfunction "2_2") (pintype "passive"))
      (node (ref "R1705") (pin "1") (pinfunction "1_1") (pintype "passive"))
    )
    (net (code "24") (name "HDMI0_TX2N_PORT") (class "Default")
      (node (ref "C1705") (pin "2") (pinfunction "2_2") (pintype "passive"))
      (node (ref "R1702") (pin "1") (pinfunction "1_1") (pintype "passive"))
    )
    (net (code "25") (name "HDMI0_TX2P_PORT") (class "Default")
      (node (ref "C1704") (pin "2") (pinfunction "2_2") (pintype "passive"))
      (node (ref "R1703") (pin "1") (pinfunction "1_1") (pintype "passive"))
    )
    (net (code "26") (name "HDMI0_TX3N_PORT") (class "Default")
      (node (ref "C1707") (pin "2") (pinfunction "2_2") (pintype "passive"))
      (node (ref "R1700") (pin "1") (pinfunction "1_1") (pintype "passive"))
    )
    (net (code "27") (name "HDMI0_TX3P_PORT") (class "Default")
      (node (ref "C1706") (pin "2") (pinfunction "2_2") (pintype "passive"))
      (node (ref "R1701") (pin "1") (pinfunction "1_1") (pintype "passive"))
    )
    (net (code "28") (name "HDMI0_TX_ON_H") (class "Default")
      (node (ref "Q1700") (pin "1") (pinfunction "GATE_1") (pintype "passive"))
      (node (ref "Q1701") (pin "1") (pinfunction "GATE_1") (pintype "passive"))
      (node (ref "Q1702") (pin "1") (pinfunction "GATE_1") (pintype "passive"))
      (node (ref "Q1703") (pin "1") (pinfunction "GATE_1") (pintype "passive"))
    )
    (net (code "29") (name "HDMI1_TX0N_PORT") (class "Default")
      (node (ref "C1717") (pin "2") (pinfunction "2_2") (pintype "passive"))
      (node (ref "R1715") (pin "1") (pinfunction "1_1") (pintype "passive"))
    )
    (net (code "30") (name "HDMI1_TX0P_PORT") (class "Default")
      (node (ref "C1716") (pin "2") (pinfunction "2_2") (pintype "passive"))
      (node (ref "R1716") (pin "1") (pinfunction "1_1") (pintype "passive"))
    )
    (net (code "31") (name "HDMI1_TX1N_PORT") (class "Default")
      (node (ref "C1719") (pin "2") (pinfunction "2_2") (pintype "passive"))
      (node (ref "R1713") (pin "1") (pinfunction "1_1") (pintype "passive"))
    )
    (net (code "32") (name "HDMI1_TX1P_PORT") (class "Default")
      (node (ref "C1718") (pin "2") (pinfunction "2_2") (pintype "passive"))
      (node (ref "R1714") (pin "1") (pinfunction "1_1") (pintype "passive"))
    )
    (net (code "33") (name "HDMI1_TX2N_PORT") (class "Default")
      (node (ref "C1721") (pin "2") (pinfunction "2_2") (pintype "passive"))
      (node (ref "R1711") (pin "1") (pinfunction "1_1") (pintype "passive"))
    )
    (net (code "34") (name "HDMI1_TX2P_PORT") (class "Default")
      (node (ref "C1720") (pin "2") (pinfunction "2_2") (pintype "passive"))
      (node (ref "R1712") (pin "1") (pinfunction "1_1") (pintype "passive"))
    )
    (net (code "35") (name "HDMI1_TX3N_PORT") (class "Default")
      (node (ref "C1723") (pin "2") (pinfunction "2_2") (pintype "passive"))
      (node (ref "R1709") (pin "1") (pinfunction "1_1") (pintype "passive"))
    )
    (net (code "36") (name "HDMI1_TX3P_PORT") (class "Default")
      (node (ref "C1722") (pin "2") (pinfunction "2_2") (pintype "passive"))
      (node (ref "R1710") (pin "1") (pinfunction "1_1") (pintype "passive"))
    )
    (net (code "37") (name "HDMI1_TX_ON_H") (class "Default")
      (node (ref "Q1704") (pin "1") (pinfunction "GATE_1") (pintype "passive"))
      (node (ref "Q1705") (pin "1") (pinfunction "GATE_1") (pintype "passive"))
      (node (ref "Q1706") (pin "1") (pinfunction "GATE_1") (pintype "passive"))
      (node (ref "Q1707") (pin "1") (pinfunction "GATE_1") (pintype "passive"))
    )
    (net (code "38") (name "Net-(Q1700-DRAIN)") (class "Default")
      (node (ref "Q1700") (pin "3") (pinfunction "DRAIN_3") (pintype "passive"))
      (node (ref "R1700") (pin "2") (pinfunction "2_2") (pintype "passive"))
      (node (ref "R1701") (pin "2") (pinfunction "2_2") (pintype "passive"))
    )
    (net (code "39") (name "Net-(Q1701-DRAIN)") (class "Default")
      (node (ref "Q1701") (pin "3") (pinfunction "DRAIN_3") (pintype "passive"))
      (node (ref "R1702") (pin "2") (pinfunction "2_2") (pintype "passive"))
      (node (ref "R1703") (pin "2") (pinfunction "2_2") (pintype "passive"))
    )
    (net (code "40") (name "Net-(Q1702-DRAIN)") (class "Default")
      (node (ref "Q1702") (pin "3") (pinfunction "DRAIN_3") (pintype "passive"))
      (node (ref "R1704") (pin "2") (pinfunction "2_2") (pintype "passive"))
      (node (ref "R1705") (pin "2") (pinfunction "2_2") (pintype "passive"))
    )
    (net (code "41") (name "Net-(Q1703-DRAIN)") (class "Default")
      (node (ref "Q1703") (pin "3") (pinfunction "DRAIN_3") (pintype "passive"))
      (node (ref "R1706") (pin "2") (pinfunction "2_2") (pintype "passive"))
      (node (ref "R1707") (pin "2") (pinfunction "2_2") (pintype "passive"))
    )
    (net (code "42") (name "Net-(Q1704-DRAIN)") (class "Default")
      (node (ref "Q1704") (pin "3") (pinfunction "DRAIN_3") (pintype "passive"))
      (node (ref "R1709") (pin "2") (pinfunction "2_2") (pintype "passive"))
      (node (ref "R1710") (pin "2") (pinfunction "2_2") (pintype "passive"))
    )
    (net (code "43") (name "Net-(Q1705-DRAIN)") (class "Default")
      (node (ref "Q1705") (pin "3") (pinfunction "DRAIN_3") (pintype "passive"))
      (node (ref "R1711") (pin "2") (pinfunction "2_2") (pintype "passive"))
      (node (ref "R1712") (pin "2") (pinfunction "2_2") (pintype "passive"))
    )
    (net (code "44") (name "Net-(Q1706-DRAIN)") (class "Default")
      (node (ref "Q1706") (pin "3") (pinfunction "DRAIN_3") (pintype "passive"))
      (node (ref "R1713") (pin "2") (pinfunction "2_2") (pintype "passive"))
      (node (ref "R1714") (pin "2") (pinfunction "2_2") (pintype "passive"))
    )
    (net (code "45") (name "Net-(Q1707-DRAIN)") (class "Default")
      (node (ref "Q1707") (pin "3") (pinfunction "DRAIN_3") (pintype "passive"))
      (node (ref "R1715") (pin "2") (pinfunction "2_2") (pintype "passive"))
      (node (ref "R1716") (pin "2") (pinfunction "2_2") (pintype "passive"))
    )
    (net (code "46") (name "VCCA1V8_IMAGE") (class "Default")
      (node (ref "C1713") (pin "1") (pinfunction "1_1") (pintype "passive"))
      (node (ref "C1714") (pin "1") (pinfunction "1_1") (pintype "passive"))
      (node (ref "C1715") (pin "1") (pinfunction "1_1") (pintype "passive"))
      (node (ref "C1729") (pin "1") (pinfunction "1_1") (pintype "passive"))
      (node (ref "C1730") (pin "1") (pinfunction "1_1") (pintype "passive"))
      (node (ref "C1731") (pin "1") (pinfunction "1_1") (pintype "passive"))
      (node (ref "U1000") (pin "AC6") (pinfunction "HDMI/EDP_TX0_VDD_CMN_1V8_AC6") (pintype "passive"))
      (node (ref "U1000") (pin "AC7") (pinfunction "HDMI/EDP_TX0_VDD_IO_1V8_AC7") (pintype "passive"))
      (node (ref "U1000") (pin "AD6") (pinfunction "HDMI/EDP_TX1_VDD_CMN_1V8_AD6") (pintype "passive"))
      (node (ref "U1000") (pin "AD7") (pinfunction "HDMI/EDP_TX1_VDD_IO_1V8_AD7") (pintype "passive"))
    )
    (net (code "47") (name "VDDA0V75_IMAGE") (class "Default")
      (node (ref "C1709") (pin "1") (pinfunction "1_1") (pintype "passive"))
      (node (ref "C1710") (pin "1") (pinfunction "1_1") (pintype "passive"))
      (node (ref "C1711") (pin "1") (pinfunction "1_1") (pintype "passive"))
      (node (ref "C1724") (pin "1") (pinfunction "1_1") (pintype "passive"))
      (node (ref "C1725") (pin "1") (pinfunction "1_1") (pintype "passive"))
      (node (ref "C1726") (pin "1") (pinfunction "1_1") (pintype "passive"))
      (node (ref "C1727") (pin "1") (pinfunction "1_1") (pintype "passive"))
      (node (ref "U1000") (pin "AA9") (pinfunction "HDMI/EDP_TX0_VDD_0V75_AA9") (pintype "passive"))
      (node (ref "U1000") (pin "AB9") (pinfunction "HDMI/EDP_TX0_AVDD_0V75_AB9") (pintype "passive"))
      (node (ref "U1000") (pin "AC9") (pinfunction "HDMI/EDP_TX1_AVDD_0V75_AC9") (pintype "passive"))
      (node (ref "U1000") (pin "AD9") (pinfunction "HDMI/EDP_TX1_VDD_0V75_AD9") (pintype "passive"))
    )
    (net (code "48") (name "unconnected-(U1000S-HDMI_TX0_SBDN{slash}EDP_TX0_AUXN-PadAG1)") (class "Default")
      (node (ref "U1000") (pin "AG1") (pinfunction "HDMI_TX0_SBDN/EDP_TX0_AUXN_AG1") (pintype "passive+no_connect"))
    )
    (net (code "49") (name "unconnected-(U1000S-HDMI_TX0_SBDP{slash}EDP_TX0_AUXP-PadAG2)") (class "Default")
      (node (ref "U1000") (pin "AG2") (pinfunction "HDMI_TX0_SBDP/EDP_TX0_AUXP_AG2") (pintype "passive+no_connect"))
    )
    (net (code "50") (name "unconnected-(U1000S-HDMI_TX1_SBDN{slash}EDP_TX1_AUXN-PadAP2)") (class "Default")
      (node (ref "U1000") (pin "AP2") (pinfunction "HDMI_TX1_SBDN/EDP_TX1_AUXN_AP2") (pintype "passive+no_connect"))
    )
    (net (code "51") (name "unconnected-(U1000S-HDMI_TX1_SBDP{slash}EDP_TX1_AUXP-PadAN2)") (class "Default")
      (node (ref "U1000") (pin "AN2") (pinfunction "HDMI_TX1_SBDP/EDP_TX1_AUXP_AN2") (pintype "passive+no_connect"))
    )
    (net (code "52") (name "unconnected-(U1000T-HDMI_RX_AVDD0V75-PadAE8)") (class "Default")
      (node (ref "U1000") (pin "AE8") (pinfunction "HDMI_RX_AVDD0V75_AE8") (pintype "passive+no_connect"))
    )
    (net (code "53") (name "unconnected-(U1000T-HDMI_RX_CLKN-PadAF5)") (class "Default")
      (node (ref "U1000") (pin "AF5") (pinfunction "HDMI_RX_CLKN_AF5") (pintype "passive+no_connect"))
    )
    (net (code "54") (name "unconnected-(U1000T-HDMI_RX_CLKP-PadAF6)") (class "Default")
      (node (ref "U1000") (pin "AF6") (pinfunction "HDMI_RX_CLKP_AF6") (pintype "passive+no_connect"))
    )
    (net (code "55") (name "unconnected-(U1000T-HDMI_RX_D0N-PadAG4)") (class "Default")
      (node (ref "U1000") (pin "AG4") (pinfunction "HDMI_RX_D0N_AG4") (pintype "passive+no_connect"))
    )
    (net (code "56") (name "unconnected-(U1000T-HDMI_RX_D0P-PadAG5)") (class "Default")
      (node (ref "U1000") (pin "AG5") (pinfunction "HDMI_RX_D0P_AG5") (pintype "passive+no_connect"))
    )
    (net (code "57") (name "unconnected-(U1000T-HDMI_RX_D1N-PadAH5)") (class "Default")
      (node (ref "U1000") (pin "AH5") (pinfunction "HDMI_RX_D1N_AH5") (pintype "passive+no_connect"))
    )
    (net (code "58") (name "unconnected-(U1000T-HDMI_RX_D1P-PadAH6)") (class "Default")
      (node (ref "U1000") (pin "AH6") (pinfunction "HDMI_RX_D1P_AH6") (pintype "passive+no_connect"))
    )
    (net (code "59") (name "unconnected-(U1000T-HDMI_RX_D2N-PadAJ4)") (class "Default")
      (node (ref "U1000") (pin "AJ4") (pinfunction "HDMI_RX_D2N_AJ4") (pintype "passive+no_connect"))
    )
    (net (code "60") (name "unconnected-(U1000T-HDMI_RX_D2P-PadAJ5)") (class "Default")
      (node (ref "U1000") (pin "AJ5") (pinfunction "HDMI_RX_D2P_AJ5") (pintype "passive+no_connect"))
    )
    (net (code "61") (name "unconnected-(U1000T-HDMI_RX_DVDD3V3-PadAE5)") (class "Default")
      (node (ref "U1000") (pin "AE5") (pinfunction "HDMI_RX_DVDD3V3_AE5") (pintype "passive+no_connect"))
    )
    (net (code "62") (name "unconnected-(U1000T-HDMI_RX_REXT-PadAF3)") (class "Default")
      (node (ref "U1000") (pin "AF3") (pinfunction "HDMI_RX_REXT_AF3") (pintype "passive+no_connect"))
    )
    (net (code "63") (name "unconnected-(U1000T-HDMI_RX_VPH3V3-PadAE4)") (class "Default")
      (node (ref "U1000") (pin "AE4") (pinfunction "HDMI_RX_VPH3V3_AE4") (pintype "passive+no_connect"))
    )
  )
)
